# Relay.net
KiCad netlist of a schematic drawn in Altium Designer
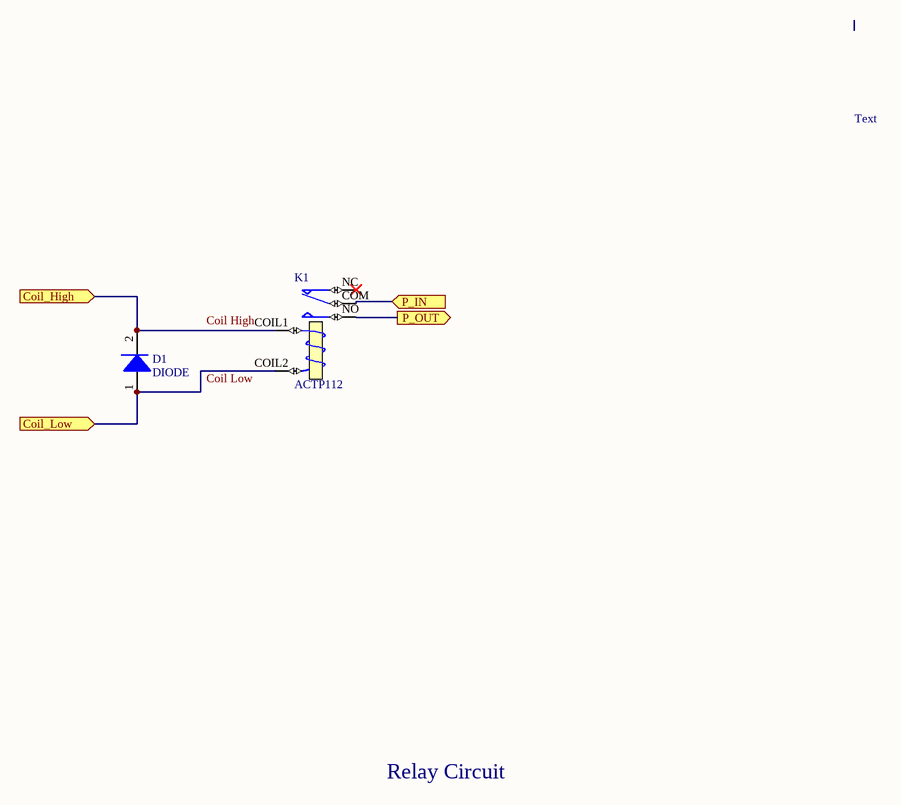
[diagram p0: Relay.SchDoc]

(export (version "E")
  (design (tool "Eeschema 10.0.6"))
  (components
    (comp (ref "D1")
      (value "DIODE")
      (footprint "SOD123F")
      (description "Diode Super Barrier 40V 1A Surface Mount SOD-123F")
      (fields (field (name "POWER") "40V") (field (name "MFRPARTNO") "1N5819HW1-7-F"))
      (libsource (lib "Altium-Lib") (part "DIODE"))
    )
    (comp (ref "K1")
      (value "ACTP112")
      (footprint "ACTP112")
      (fields (field (name "PUBLISHER") "Altium Limited"))
      (libsource (lib "Altium-Lib") (part "ACTP112"))
    )
  )
  (nets
    (net (code "3") (name "/Coil_High") (class "Default")
      (node (ref "D1") (pin "2") (pinfunction "K_2") (pintype "passive"))
      (node (ref "K1") (pin "COIL1") (pinfunction "T1_COIL1") (pintype "bidirectional"))
    )
    (net (code "4") (name "/Coil_Low") (class "Default")
      (node (ref "D1") (pin "1") (pinfunction "A_1") (pintype "passive"))
      (node (ref "K1") (pin "COIL2") (pinfunction "T2_COIL2") (pintype "bidirectional"))
    )
    (net (code "5") (name "/P_IN") (class "Default")
      (node (ref "K1") (pin "COM") (pinfunction "COM_COM") (pintype "bidirectional"))
    )
    (net (code "6") (name "/P_OUT") (class "Default")
      (node (ref "K1") (pin "NO") (pinfunction "NO_NO") (pintype "bidirectional"))
    )
    (net (code "7") (name "unconnected-(K1-PadNC)") (class "Default")
      (node (ref "K1") (pin "NC") (pinfunction "NC_NC") (pintype "bidirectional+no_connect"))
    )
  )
)
